# comms_sys_schematic_no_ch340G.net
KiCad netlist of a schematic drawn in EAGLE
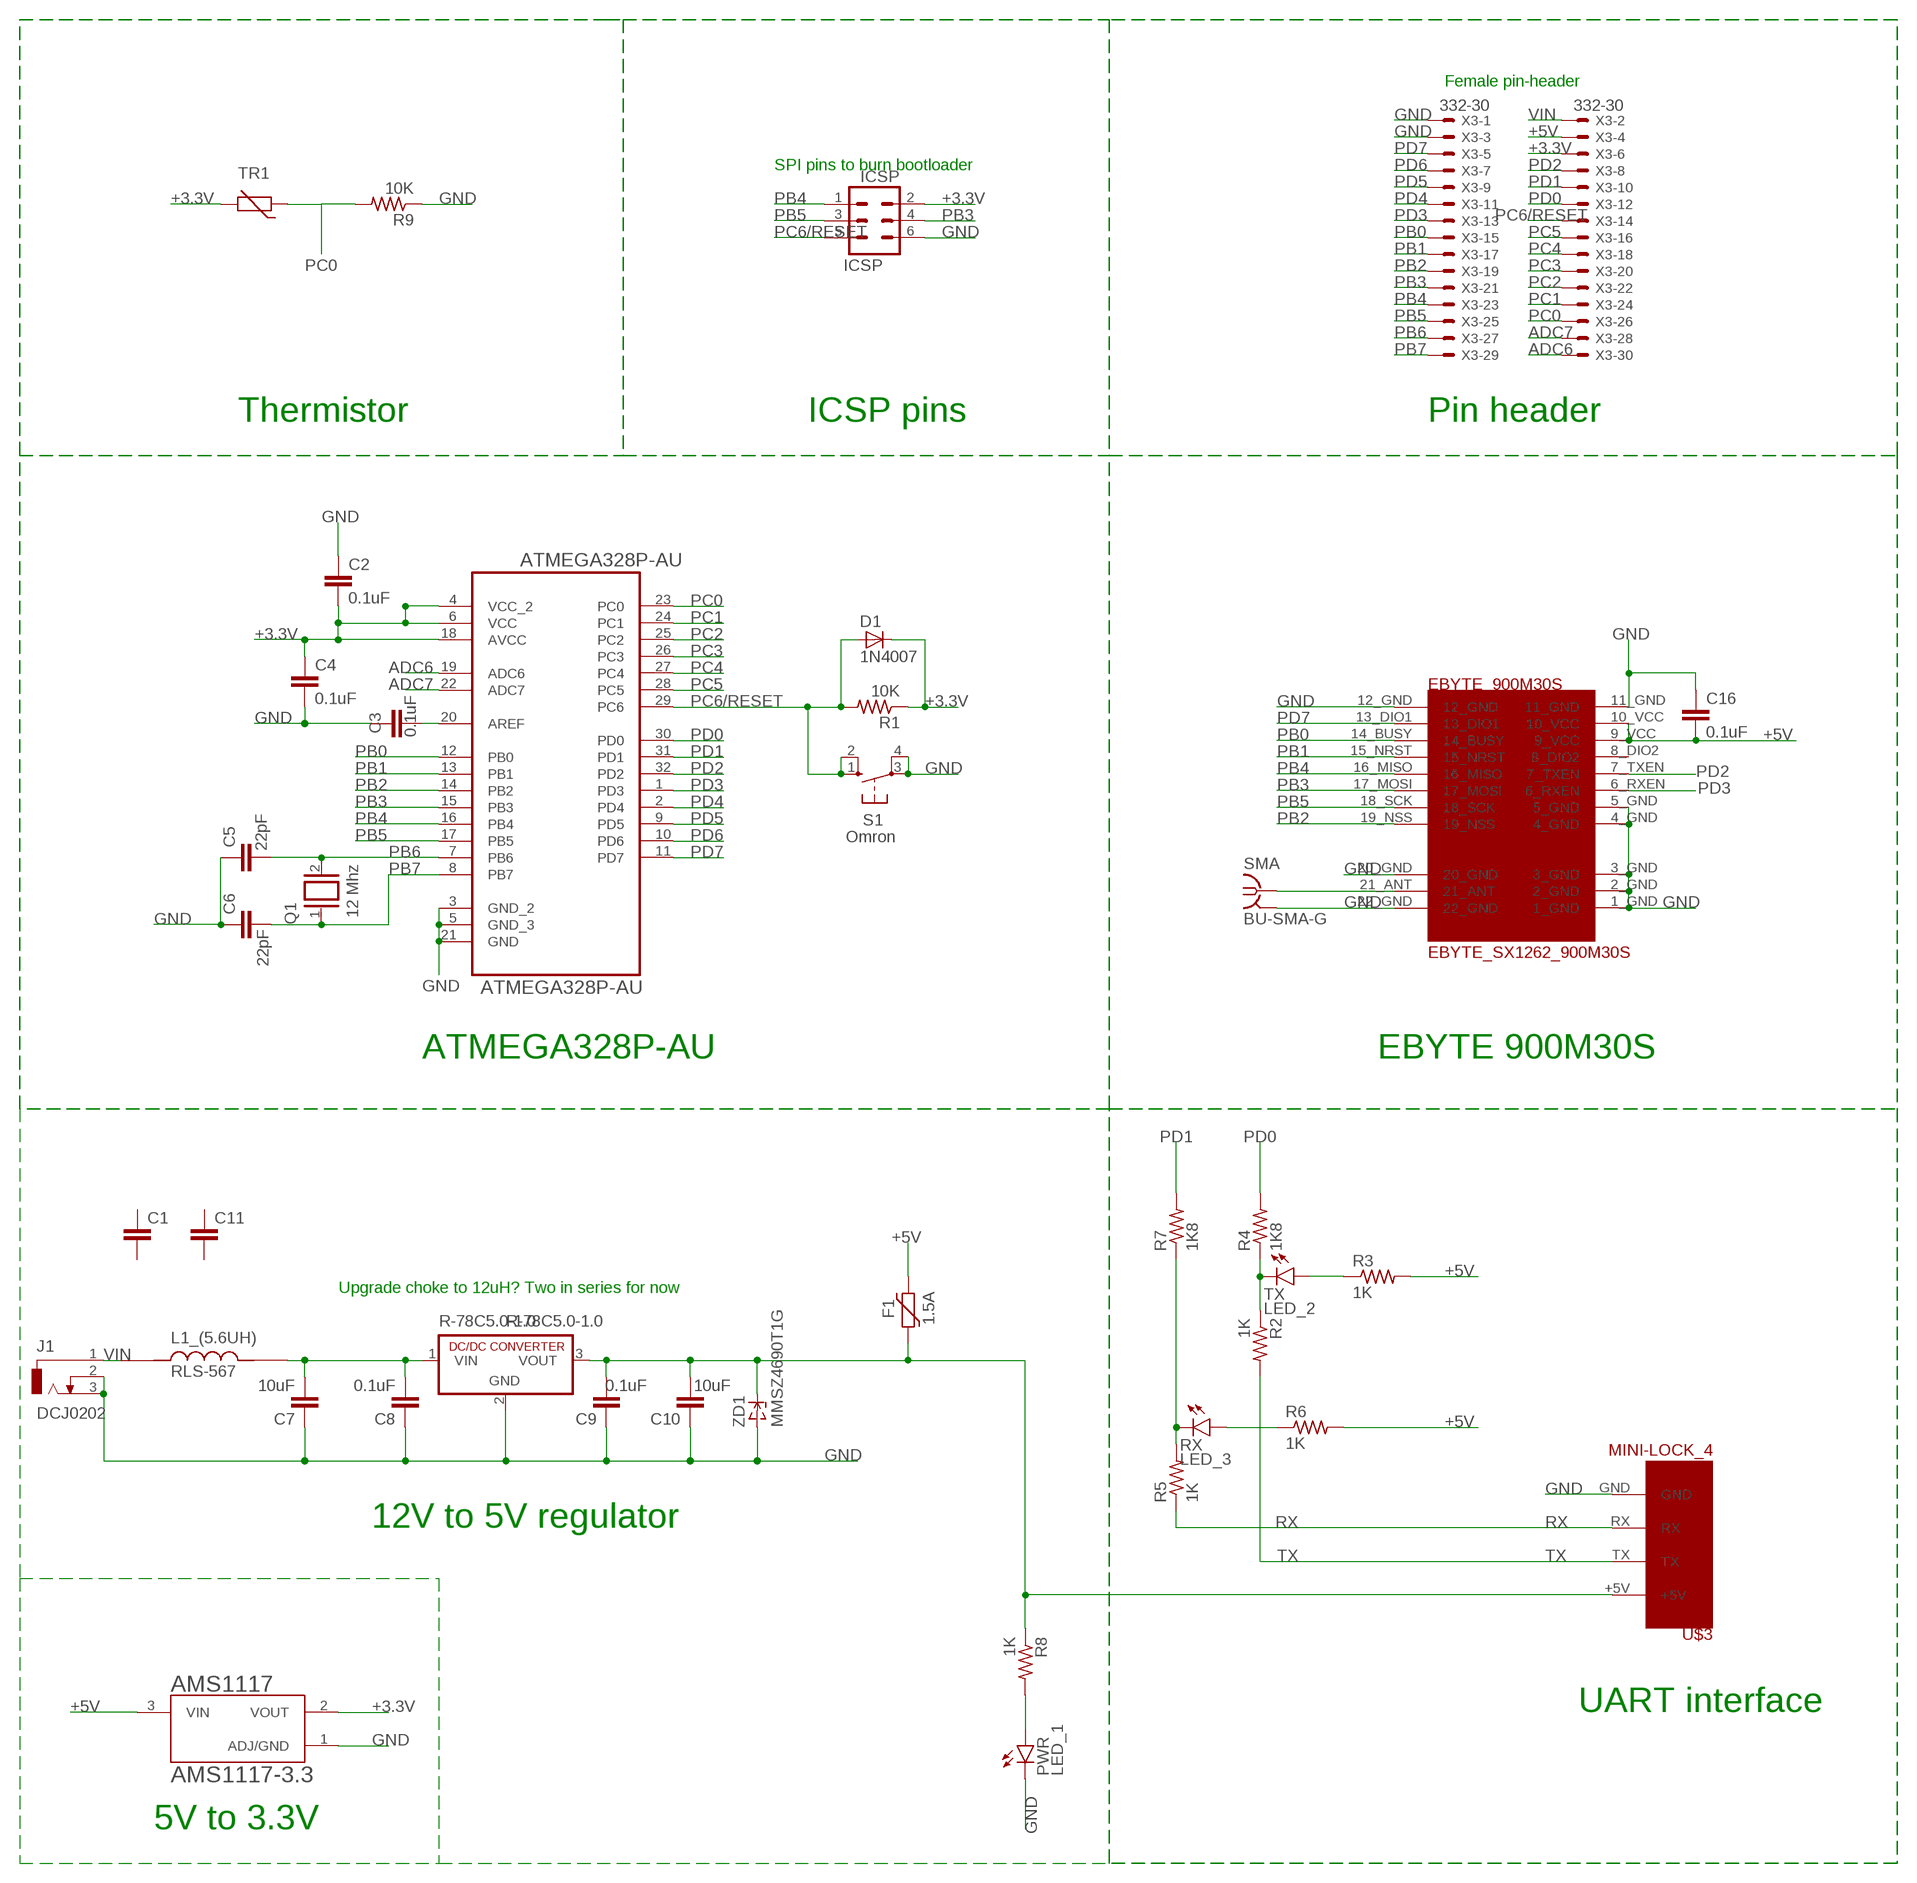
[diagram p0: schematic, sheet 1]

(export (version "E")
  (design (tool "Eeschema 10.0.6"))
  (components
    (comp (ref "AMS1117")
      (value "AMS1117-3.3")
      (footprint "eagle-import:SOT229P700X180-4N")
      (fields (field (name "MF") "Advanced Monolithic Systems"))
      (libsource (lib "eagle-import") (part "AMS1117-3.3"))
    )
    (comp (ref "ATMEGA328P-AU")
      (value "ATMEGA328P-AU")
      (footprint "eagle-import:QFP80P900X900X120-32N")
      (libsource (lib "eagle-import") (part "ATMEGA328P-AU"))
    )
    (comp (ref "C1")
      (value "C-EUC1206")
      (footprint "eagle-import:C1206")
      (libsource (lib "eagle-import") (part "C-EUC1206"))
    )
    (comp (ref "C2")
      (value "0.1uF")
      (footprint "eagle-import:C0805")
      (libsource (lib "eagle-import") (part "C-EUC0805"))
    )
    (comp (ref "C3")
      (value "0.1uF")
      (footprint "eagle-import:C0805")
      (libsource (lib "eagle-import") (part "C-EUC0805"))
    )
    (comp (ref "C4")
      (value "0.1uF")
      (footprint "eagle-import:C0805")
      (libsource (lib "eagle-import") (part "C-EUC0805"))
    )
    (comp (ref "C5")
      (value "22pF")
      (footprint "eagle-import:C0805")
      (libsource (lib "eagle-import") (part "C-EUC0805"))
    )
    (comp (ref "C6")
      (value "22pF")
      (footprint "eagle-import:C0805")
      (libsource (lib "eagle-import") (part "C-EUC0805"))
    )
    (comp (ref "C7")
      (value "10uF")
      (footprint "eagle-import:C0805")
      (libsource (lib "eagle-import") (part "C-EUC0805"))
    )
    (comp (ref "C8")
      (value "0.1uF")
      (footprint "eagle-import:C0805")
      (libsource (lib "eagle-import") (part "C-EUC0805"))
    )
    (comp (ref "C9")
      (value "0.1uF")
      (footprint "eagle-import:C0805")
      (libsource (lib "eagle-import") (part "C-EUC0805"))
    )
    (comp (ref "C10")
      (value "10uF")
      (footprint "eagle-import:C0805")
      (libsource (lib "eagle-import") (part "C-EUC0805"))
    )
    (comp (ref "C11")
      (value "C-EUC1206")
      (footprint "eagle-import:C1206")
      (libsource (lib "eagle-import") (part "C-EUC1206"))
    )
    (comp (ref "C16")
      (value "0.1uF")
      (footprint "eagle-import:C0805")
      (libsource (lib "eagle-import") (part "C-EUC0805"))
    )
    (comp (ref "D1")
      (value "1N4007")
      (footprint "eagle-import:SMA")
      (libsource (lib "eagle-import") (part "1N4007"))
    )
    (comp (ref "EBYTE_900M30S")
      (value "EBYTE_SX1262_900M30S")
      (footprint "eagle-import:EBYTE_SX1262_900M30S_FOOTPRINT")
      (libsource (lib "eagle-import") (part "EBYTE_SX1262_900M30S"))
    )
    (comp (ref "F1")
      (value "1.5A")
      (footprint "eagle-import:PTC0805")
      (libsource (lib "eagle-import") (part "FUSE_PTC-0805"))
    )
    (comp (ref "ICSP")
      (value "ICSP")
      (footprint "eagle-import:MA03-2")
      (libsource (lib "eagle-import") (part "MA03-2"))
    )
    (comp (ref "J1")
      (value "DCJ0202")
      (footprint "eagle-import:DCJ0202")
      (libsource (lib "eagle-import") (part "DCJ0202"))
    )
    (comp (ref "L1_(5.6UH)")
      (value "RLS-567")
      (footprint "eagle-import:IND_RLS-567")
      (fields (field (name "MF") "Recom Power"))
      (libsource (lib "eagle-import") (part "RLS-567"))
    )
    (comp (ref "PWR")
      (value "LED_1")
      (footprint "eagle-import:CHIP-LED0805")
      (libsource (lib "eagle-import") (part "LEDCHIP-LED0805"))
    )
    (comp (ref "Q1")
      (value "12 Mhz")
      (footprint "eagle-import:QS")
      (libsource (lib "eagle-import") (part "XTAL/S"))
    )
    (comp (ref "R-78C5.0-1.0")
      (value "R-78C5.0-1.0")
      (footprint "eagle-import:SIP3")
      (libsource (lib "eagle-import") (part "R-78C-1.05.0"))
    )
    (comp (ref "R1")
      (value "10K")
      (footprint "eagle-import:R0805")
      (libsource (lib "eagle-import") (part "R-US_R0805"))
    )
    (comp (ref "R2")
      (value "1K")
      (footprint "eagle-import:R0805")
      (libsource (lib "eagle-import") (part "R-US_R0805"))
    )
    (comp (ref "R3")
      (value "1K")
      (footprint "eagle-import:R0805")
      (libsource (lib "eagle-import") (part "R-US_R0805"))
    )
    (comp (ref "R4")
      (value "1K8")
      (footprint "eagle-import:R0805")
      (libsource (lib "eagle-import") (part "R-US_R0805"))
    )
    (comp (ref "R5")
      (value "1K")
      (footprint "eagle-import:R0805")
      (libsource (lib "eagle-import") (part "R-US_R0805"))
    )
    (comp (ref "R6")
      (value "1K")
      (footprint "eagle-import:R0805")
      (libsource (lib "eagle-import") (part "R-US_R0805"))
    )
    (comp (ref "R7")
      (value "1K8")
      (footprint "eagle-import:R0805")
      (libsource (lib "eagle-import") (part "R-US_R0805"))
    )
    (comp (ref "R8")
      (value "1K")
      (footprint "eagle-import:R0805")
      (libsource (lib "eagle-import") (part "R-US_R0805"))
    )
    (comp (ref "R9")
      (value "10K")
      (footprint "eagle-import:R0805")
      (libsource (lib "eagle-import") (part "R-US_R0805"))
    )
    (comp (ref "RX")
      (value "LED_3")
      (footprint "eagle-import:CHIP-LED0805")
      (libsource (lib "eagle-import") (part "LEDCHIP-LED0805"))
    )
    (comp (ref "S1")
      (value "Omron")
      (footprint "eagle-import:B3F-10XX")
      (fields (field (name "MPN") "B3F-1000"))
      (libsource (lib "eagle-import") (part "10-XX"))
    )
    (comp (ref "SMA")
      (value "BU-SMA-G")
      (footprint "eagle-import:BU-SMA-G")
      (libsource (lib "eagle-import") (part "BU-SMA-G"))
    )
    (comp (ref "TR1")
      (value "THERMISTOR_R-2,5")
      (footprint "eagle-import:RS-2,5")
      (libsource (lib "eagle-import") (part "THERMISTOR_R-2,5"))
    )
    (comp (ref "TX")
      (value "LED_2")
      (footprint "eagle-import:CHIP-LED0805")
      (libsource (lib "eagle-import") (part "LEDCHIP-LED0805"))
    )
    (comp (ref "U$3")
      (value "MINI-LOCK_4")
      (footprint "eagle-import:MINI-LOCK_4")
      (libsource (lib "eagle-import") (part "MINI-LOCK_4"))
    )
    (comp (ref "X3")
      (value "332-30")
      (footprint "eagle-import:332-30")
      (libsource (lib "eagle-import") (part "332-30"))
    )
    (comp (ref "ZD1")
      (value "MMSZ4690T1G")
      (footprint "eagle-import:SOD-123")
      (libsource (lib "eagle-import") (part "ZENERSOD-123"))
    )
  )
  (nets
    (net (code "1") (name "/+3.3V") (class "Default")
      (node (ref "AMS1117") (pin "2") (pinfunction "VOUT_2") (pintype "output"))
      (node (ref "ATMEGA328P-AU") (pin "18") (pinfunction "AVCC_18") (pintype "power_in"))
      (node (ref "ATMEGA328P-AU") (pin "4") (pinfunction "VCC_2_4") (pintype "power_in"))
      (node (ref "ATMEGA328P-AU") (pin "6") (pinfunction "VCC_6") (pintype "power_in"))
      (node (ref "C2") (pin "2") (pinfunction "2_2") (pintype "passive"))
      (node (ref "C4") (pin "1") (pinfunction "1_1") (pintype "passive"))
      (node (ref "D1") (pin "K") (pinfunction "C_K") (pintype "passive"))
      (node (ref "ICSP") (pin "2") (pinfunction "2_2") (pintype "passive"))
      (node (ref "R1") (pin "1") (pinfunction "1_1") (pintype "passive"))
      (node (ref "TR1") (pin "2") (pinfunction "2_2") (pintype "passive"))
      (node (ref "X3") (pin "6") (pinfunction "S_6") (pintype "passive"))
    )
    (net (code "2") (name "/+5V") (class "Default")
      (node (ref "AMS1117") (pin "3") (pinfunction "VIN_3") (pintype "input"))
      (node (ref "C16") (pin "2") (pinfunction "2_2") (pintype "passive"))
      (node (ref "EBYTE_900M30S") (pin "10_VCC") (pinfunction "10_VCC_10_VCC") (pintype "power_in"))
      (node (ref "EBYTE_900M30S") (pin "9_VCC") (pinfunction "9_VCC_9_VCC") (pintype "power_in"))
      (node (ref "F1") (pin "2") (pinfunction "2_2") (pintype "passive"))
      (node (ref "R3") (pin "2") (pinfunction "2_2") (pintype "passive"))
      (node (ref "R6") (pin "2") (pinfunction "2_2") (pintype "passive"))
      (node (ref "X3") (pin "4") (pinfunction "S_4") (pintype "passive"))
    )
    (net (code "3") (name "/ADC6") (class "Default")
      (node (ref "ATMEGA328P-AU") (pin "19") (pinfunction "ADC6_19") (pintype "input"))
      (node (ref "X3") (pin "30") (pinfunction "S_30") (pintype "passive"))
    )
    (net (code "4") (name "/ADC7") (class "Default")
      (node (ref "ATMEGA328P-AU") (pin "22") (pinfunction "ADC7_22") (pintype "input"))
      (node (ref "X3") (pin "28") (pinfunction "S_28") (pintype "passive"))
    )
    (net (code "5") (name "/GND") (class "Default")
      (node (ref "AMS1117") (pin "1") (pinfunction "ADJ/GND_1") (pintype "power_in"))
      (node (ref "ATMEGA328P-AU") (pin "21") (pinfunction "GND_21") (pintype "passive"))
      (node (ref "ATMEGA328P-AU") (pin "3") (pinfunction "GND_2_3") (pintype "passive"))
      (node (ref "ATMEGA328P-AU") (pin "5") (pinfunction "GND_3_5") (pintype "passive"))
      (node (ref "C10") (pin "1") (pinfunction "1_1") (pintype "passive"))
      (node (ref "C16") (pin "1") (pinfunction "1_1") (pintype "passive"))
      (node (ref "C2") (pin "1") (pinfunction "1_1") (pintype "passive"))
      (node (ref "C3") (pin "1") (pinfunction "1_1") (pintype "passive"))
      (node (ref "C4") (pin "2") (pinfunction "2_2") (pintype "passive"))
      (node (ref "C5") (pin "1") (pinfunction "1_1") (pintype "passive"))
      (node (ref "C6") (pin "1") (pinfunction "1_1") (pintype "passive"))
      (node (ref "C7") (pin "1") (pinfunction "1_1") (pintype "passive"))
      (node (ref "C8") (pin "1") (pinfunction "1_1") (pintype "passive"))
      (node (ref "C9") (pin "1") (pinfunction "1_1") (pintype "passive"))
      (node (ref "EBYTE_900M30S") (pin "11_GND") (pinfunction "11_GND_11_GND") (pintype "power_in"))
      (node (ref "EBYTE_900M30S") (pin "12_GND") (pinfunction "12_GND_12_GND") (pintype "power_in"))
      (node (ref "EBYTE_900M30S") (pin "1_GND") (pinfunction "1_GND_1_GND") (pintype "power_in"))
      (node (ref "EBYTE_900M30S") (pin "20_GND") (pinfunction "20_GND_20_GND") (pintype "power_in"))
      (node (ref "EBYTE_900M30S") (pin "22_GND") (pinfunction "22_GND_22_GND") (pintype "power_in"))
      (node (ref "EBYTE_900M30S") (pin "2_GND") (pinfunction "2_GND_2_GND") (pintype "power_in"))
      (node (ref "EBYTE_900M30S") (pin "3_GND") (pinfunction "3_GND_3_GND") (pintype "power_in"))
      (node (ref "EBYTE_900M30S") (pin "4_GND") (pinfunction "4_GND_4_GND") (pintype "power_in"))
      (node (ref "EBYTE_900M30S") (pin "5_GND") (pinfunction "5_GND_5_GND") (pintype "power_in"))
      (node (ref "ICSP") (pin "6") (pinfunction "6_6") (pintype "passive"))
      (node (ref "J1") (pin "2") (pinfunction "2_2") (pintype "passive"))
      (node (ref "J1") (pin "3") (pinfunction "3_3") (pintype "passive"))
      (node (ref "PWR") (pin "C") (pinfunction "C_C") (pintype "passive"))
      (node (ref "R-78C5.0-1.0") (pin "2") (pinfunction "GND_2") (pintype "passive"))
      (node (ref "R9") (pin "1") (pinfunction "1_1") (pintype "passive"))
      (node (ref "S1") (pin "3") (pinfunction "P_3") (pintype "passive"))
      (node (ref "S1") (pin "4") (pinfunction "P1_4") (pintype "passive"))
      (node (ref "SMA") (pin "2") (pinfunction "2_2") (pintype "passive"))
      (node (ref "SMA") (pin "3") (pinfunction "2_3") (pintype "passive"))
      (node (ref "SMA") (pin "4") (pinfunction "2_4") (pintype "passive"))
      (node (ref "SMA") (pin "5") (pinfunction "2_5") (pintype "passive"))
      (node (ref "U$3") (pin "GND") (pinfunction "GND_GND") (pintype "bidirectional"))
      (node (ref "X3") (pin "1") (pinfunction "S_1") (pintype "passive"))
      (node (ref "X3") (pin "3") (pinfunction "S_3") (pintype "passive"))
      (node (ref "ZD1") (pin "A") (pinfunction "A_A") (pintype "passive"))
    )
    (net (code "6") (name "/PB0") (class "Default")
      (node (ref "ATMEGA328P-AU") (pin "12") (pinfunction "PB0_12") (pintype "bidirectional"))
      (node (ref "EBYTE_900M30S") (pin "14_BUSY") (pinfunction "14_BUSY_14_BUSY") (pintype "bidirectional"))
      (node (ref "X3") (pin "15") (pinfunction "S_15") (pintype "passive"))
    )
    (net (code "7") (name "/PB1") (class "Default")
      (node (ref "ATMEGA328P-AU") (pin "13") (pinfunction "PB1_13") (pintype "bidirectional"))
      (node (ref "EBYTE_900M30S") (pin "15_NRST") (pinfunction "15_NRST_15_NRST") (pintype "bidirectional"))
      (node (ref "X3") (pin "17") (pinfunction "S_17") (pintype "passive"))
    )
    (net (code "8") (name "/PB2") (class "Default")
      (node (ref "ATMEGA328P-AU") (pin "14") (pinfunction "PB2_14") (pintype "bidirectional"))
      (node (ref "EBYTE_900M30S") (pin "19_NSS") (pinfunction "19_NSS_19_NSS") (pintype "bidirectional"))
      (node (ref "X3") (pin "19") (pinfunction "S_19") (pintype "passive"))
    )
    (net (code "9") (name "/PB3") (class "Default")
      (node (ref "ATMEGA328P-AU") (pin "15") (pinfunction "PB3_15") (pintype "bidirectional"))
      (node (ref "EBYTE_900M30S") (pin "17_MOSI") (pinfunction "17_MOSI_17_MOSI") (pintype "bidirectional"))
      (node (ref "ICSP") (pin "4") (pinfunction "4_4") (pintype "passive"))
      (node (ref "X3") (pin "21") (pinfunction "S_21") (pintype "passive"))
    )
    (net (code "10") (name "/PB4") (class "Default")
      (node (ref "ATMEGA328P-AU") (pin "16") (pinfunction "PB4_16") (pintype "bidirectional"))
      (node (ref "EBYTE_900M30S") (pin "16_MISO") (pinfunction "16_MISO_16_MISO") (pintype "bidirectional"))
      (node (ref "ICSP") (pin "1") (pinfunction "1_1") (pintype "passive"))
      (node (ref "X3") (pin "23") (pinfunction "S_23") (pintype "passive"))
    )
    (net (code "11") (name "/PB5") (class "Default")
      (node (ref "ATMEGA328P-AU") (pin "17") (pinfunction "PB5_17") (pintype "bidirectional"))
      (node (ref "EBYTE_900M30S") (pin "18_SCK") (pinfunction "18_SCK_18_SCK") (pintype "bidirectional"))
      (node (ref "ICSP") (pin "3") (pinfunction "3_3") (pintype "passive"))
      (node (ref "X3") (pin "25") (pinfunction "S_25") (pintype "passive"))
    )
    (net (code "12") (name "/PB6") (class "Default")
      (node (ref "ATMEGA328P-AU") (pin "7") (pinfunction "PB6_7") (pintype "bidirectional"))
      (node (ref "C5") (pin "2") (pinfunction "2_2") (pintype "passive"))
      (node (ref "Q1") (pin "2") (pinfunction "2_2") (pintype "passive"))
      (node (ref "X3") (pin "27") (pinfunction "S_27") (pintype "passive"))
    )
    (net (code "13") (name "/PB7") (class "Default")
      (node (ref "ATMEGA328P-AU") (pin "8") (pinfunction "PB7_8") (pintype "bidirectional"))
      (node (ref "C6") (pin "2") (pinfunction "2_2") (pintype "passive"))
      (node (ref "Q1") (pin "1") (pinfunction "1_1") (pintype "passive"))
      (node (ref "X3") (pin "29") (pinfunction "S_29") (pintype "passive"))
    )
    (net (code "14") (name "/PC0") (class "Default")
      (node (ref "ATMEGA328P-AU") (pin "23") (pinfunction "PC0_23") (pintype "bidirectional"))
      (node (ref "R9") (pin "2") (pinfunction "2_2") (pintype "passive"))
      (node (ref "TR1") (pin "1") (pinfunction "1_1") (pintype "passive"))
      (node (ref "X3") (pin "26") (pinfunction "S_26") (pintype "passive"))
    )
    (net (code "15") (name "/PC1") (class "Default")
      (node (ref "ATMEGA328P-AU") (pin "24") (pinfunction "PC1_24") (pintype "bidirectional"))
      (node (ref "X3") (pin "24") (pinfunction "S_24") (pintype "passive"))
    )
    (net (code "16") (name "/PC2") (class "Default")
      (node (ref "ATMEGA328P-AU") (pin "25") (pinfunction "PC2_25") (pintype "bidirectional"))
      (node (ref "X3") (pin "22") (pinfunction "S_22") (pintype "passive"))
    )
    (net (code "17") (name "/PC3") (class "Default")
      (node (ref "ATMEGA328P-AU") (pin "26") (pinfunction "PC3_26") (pintype "bidirectional"))
      (node (ref "X3") (pin "20") (pinfunction "S_20") (pintype "passive"))
    )
    (net (code "18") (name "/PC4") (class "Default")
      (node (ref "ATMEGA328P-AU") (pin "27") (pinfunction "PC4_27") (pintype "bidirectional"))
      (node (ref "X3") (pin "18") (pinfunction "S_18") (pintype "passive"))
    )
    (net (code "19") (name "/PC5") (class "Default")
      (node (ref "ATMEGA328P-AU") (pin "28") (pinfunction "PC5_28") (pintype "bidirectional"))
      (node (ref "X3") (pin "16") (pinfunction "S_16") (pintype "passive"))
    )
    (net (code "20") (name "/PC6{slash}RESET") (class "Default")
      (node (ref "ATMEGA328P-AU") (pin "29") (pinfunction "PC6_29") (pintype "bidirectional"))
      (node (ref "D1") (pin "A") (pinfunction "A_A") (pintype "passive"))
      (node (ref "ICSP") (pin "5") (pinfunction "5_5") (pintype "passive"))
      (node (ref "R1") (pin "2") (pinfunction "2_2") (pintype "passive"))
      (node (ref "S1") (pin "1") (pinfunction "S_1") (pintype "passive"))
      (node (ref "S1") (pin "2") (pinfunction "S1_2") (pintype "passive"))
      (node (ref "X3") (pin "14") (pinfunction "S_14") (pintype "passive"))
    )
    (net (code "21") (name "/PD0") (class "Default")
      (node (ref "ATMEGA328P-AU") (pin "30") (pinfunction "PD0_30") (pintype "bidirectional"))
      (node (ref "R4") (pin "2") (pinfunction "2_2") (pintype "passive"))
      (node (ref "X3") (pin "12") (pinfunction "S_12") (pintype "passive"))
    )
    (net (code "22") (name "/PD1") (class "Default")
      (node (ref "ATMEGA328P-AU") (pin "31") (pinfunction "PD1_31") (pintype "bidirectional"))
      (node (ref "R7") (pin "2") (pinfunction "2_2") (pintype "passive"))
      (node (ref "X3") (pin "10") (pinfunction "S_10") (pintype "passive"))
    )
    (net (code "23") (name "/PD2") (class "Default")
      (node (ref "ATMEGA328P-AU") (pin "32") (pinfunction "PD2_32") (pintype "bidirectional"))
      (node (ref "EBYTE_900M30S") (pin "7_TXEN") (pinfunction "7_TXEN_7_TXEN") (pintype "bidirectional"))
      (node (ref "X3") (pin "8") (pinfunction "S_8") (pintype "passive"))
    )
    (net (code "24") (name "/PD3") (class "Default")
      (node (ref "ATMEGA328P-AU") (pin "1") (pinfunction "PD3_1") (pintype "bidirectional"))
      (node (ref "EBYTE_900M30S") (pin "6_RXEN") (pinfunction "6_RXEN_6_RXEN") (pintype "bidirectional"))
      (node (ref "X3") (pin "13") (pinfunction "S_13") (pintype "passive"))
    )
    (net (code "25") (name "/PD4") (class "Default")
      (node (ref "ATMEGA328P-AU") (pin "2") (pinfunction "PD4_2") (pintype "bidirectional"))
      (node (ref "X3") (pin "11") (pinfunction "S_11") (pintype "passive"))
    )
    (net (code "26") (name "/PD5") (class "Default")
      (node (ref "ATMEGA328P-AU") (pin "9") (pinfunction "PD5_9") (pintype "bidirectional"))
      (node (ref "X3") (pin "9") (pinfunction "S_9") (pintype "passive"))
    )
    (net (code "27") (name "/PD6") (class "Default")
      (node (ref "ATMEGA328P-AU") (pin "10") (pinfunction "PD6_10") (pintype "bidirectional"))
      (node (ref "X3") (pin "7") (pinfunction "S_7") (pintype "passive"))
    )
    (net (code "28") (name "/PD7") (class "Default")
      (node (ref "ATMEGA328P-AU") (pin "11") (pinfunction "PD7_11") (pintype "bidirectional"))
      (node (ref "EBYTE_900M30S") (pin "13_DIO1") (pinfunction "13_DIO1_13_DIO1") (pintype "bidirectional"))
      (node (ref "X3") (pin "5") (pinfunction "S_5") (pintype "passive"))
    )
    (net (code "29") (name "/RX") (class "Default")
      (node (ref "R5") (pin "1") (pinfunction "1_1") (pintype "passive"))
      (node (ref "U$3") (pin "RX") (pinfunction "RX_RX") (pintype "bidirectional"))
    )
    (net (code "30") (name "/TX") (class "Default")
      (node (ref "R2") (pin "2") (pinfunction "2_2") (pintype "passive"))
      (node (ref "U$3") (pin "TX") (pinfunction "TX_TX") (pintype "bidirectional"))
    )
    (net (code "31") (name "/VIN") (class "Default")
      (node (ref "J1") (pin "1") (pinfunction "1_1") (pintype "passive"))
      (node (ref "L1_(5.6UH)") (pin "1") (pinfunction "1_1") (pintype "passive"))
      (node (ref "X3") (pin "2") (pinfunction "S_2") (pintype "passive"))
    )
    (net (code "32") (name "Net-(ATMEGA328P-AU-AREF)") (class "Default")
      (node (ref "ATMEGA328P-AU") (pin "20") (pinfunction "AREF_20") (pintype "input"))
      (node (ref "C3") (pin "2") (pinfunction "2_2") (pintype "passive"))
    )
    (net (code "33") (name "Net-(EBYTE_900M30S-Pad21_ANT)") (class "Default")
      (node (ref "EBYTE_900M30S") (pin "21_ANT") (pinfunction "21_ANT_21_ANT") (pintype "bidirectional"))
      (node (ref "SMA") (pin "1") (pinfunction "1_1") (pintype "passive"))
    )
    (net (code "34") (name "Net-(PWR-PadA)") (class "Default")
      (node (ref "PWR") (pin "A") (pinfunction "A_A") (pintype "passive"))
      (node (ref "R8") (pin "2") (pinfunction "2_2") (pintype "passive"))
    )
    (net (code "35") (name "Net-(R-78C5.0-1.0-VIN)") (class "Default")
      (node (ref "C7") (pin "2") (pinfunction "2_2") (pintype "passive"))
      (node (ref "C8") (pin "2") (pinfunction "2_2") (pintype "passive"))
      (node (ref "L1_(5.6UH)") (pin "2") (pinfunction "2_2") (pintype "passive"))
      (node (ref "R-78C5.0-1.0") (pin "1") (pinfunction "VIN_1") (pintype "passive"))
    )
    (net (code "36") (name "Net-(R-78C5.0-1.0-VOUT)") (class "Default")
      (node (ref "C10") (pin "2") (pinfunction "2_2") (pintype "passive"))
      (node (ref "C9") (pin "2") (pinfunction "2_2") (pintype "passive"))
      (node (ref "F1") (pin "1") (pinfunction "1_1") (pintype "passive"))
      (node (ref "R-78C5.0-1.0") (pin "3") (pinfunction "VOUT_3") (pintype "passive"))
      (node (ref "R8") (pin "1") (pinfunction "1_1") (pintype "passive"))
      (node (ref "U$3") (pin "+5V") (pinfunction "+5V_+5V") (pintype "bidirectional"))
      (node (ref "ZD1") (pin "C") (pinfunction "C_C") (pintype "passive"))
    )
    (net (code "37") (name "Net-(R2-Pad1)") (class "Default")
      (node (ref "R2") (pin "1") (pinfunction "1_1") (pintype "passive"))
      (node (ref "R4") (pin "1") (pinfunction "1_1") (pintype "passive"))
      (node (ref "TX") (pin "C") (pinfunction "C_C") (pintype "passive"))
    )
    (net (code "38") (name "Net-(R3-Pad1)") (class "Default")
      (node (ref "R3") (pin "1") (pinfunction "1_1") (pintype "passive"))
      (node (ref "TX") (pin "A") (pinfunction "A_A") (pintype "passive"))
    )
    (net (code "39") (name "Net-(R5-Pad2)") (class "Default")
      (node (ref "R5") (pin "2") (pinfunction "2_2") (pintype "passive"))
      (node (ref "R7") (pin "1") (pinfunction "1_1") (pintype "passive"))
      (node (ref "RX") (pin "C") (pinfunction "C_C") (pintype "passive"))
    )
    (net (code "40") (name "Net-(R6-Pad1)") (class "Default")
      (node (ref "R6") (pin "1") (pinfunction "1_1") (pintype "passive"))
      (node (ref "RX") (pin "A") (pinfunction "A_A") (pintype "passive"))
    )
    (net (code "41") (name "unconnected-(C1-Pad1)") (class "Default")
      (node (ref "C1") (pin "1") (pinfunction "1_1") (pintype "passive"))
    )
    (net (code "42") (name "unconnected-(C1-Pad2)") (class "Default")
      (node (ref "C1") (pin "2") (pinfunction "2_2") (pintype "passive"))
    )
    (net (code "43") (name "unconnected-(C11-Pad1)") (class "Default")
      (node (ref "C11") (pin "1") (pinfunction "1_1") (pintype "passive"))
    )
    (net (code "44") (name "unconnected-(C11-Pad2)") (class "Default")
      (node (ref "C11") (pin "2") (pinfunction "2_2") (pintype "passive"))
    )
    (net (code "45") (name "unconnected-(EBYTE_900M30S-Pad8_DIO2)") (class "Default")
      (node (ref "EBYTE_900M30S") (pin "8_DIO2") (pinfunction "8_DIO2_8_DIO2") (pintype "bidirectional"))
    )
  )
)
